# Lights.net
KiCad netlist of a schematic drawn in Altium Designer
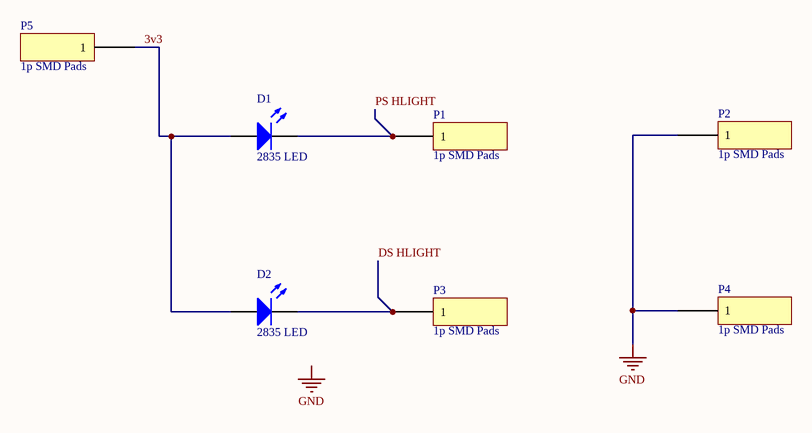
[diagram p0: Lights.SchDoc]

(export (version "E")
  (design (tool "Eeschema 10.0.6"))
  (components
    (comp (ref "D1")
      (value "2835 LED")
      (footprint "2835 LED")
      (description "White LED Songxin Light")
      (libsource (lib "parts (fraker's conflicted copy 2018-10-08)") (part "2835 LED"))
    )
    (comp (ref "D2")
      (value "2835 LED")
      (footprint "2835 LED")
      (description "White LED Songxin Light")
      (libsource (lib "parts (fraker's conflicted copy 2018-10-08)") (part "2835 LED"))
    )
    (comp (ref "P1") (value "1p SMD Pads") (footprint "1p SMD pad") (libsource (lib "parts") (part "1p SMD")))
    (comp (ref "P2") (value "1p SMD Pads") (footprint "1p SMD pad") (libsource (lib "") (part "1p SMD_2")))
    (comp (ref "P3") (value "1p SMD Pads") (footprint "1p SMD pad") (libsource (lib "parts") (part "1p SMD")))
    (comp (ref "P4") (value "1p SMD Pads") (footprint "1p SMD pad") (libsource (lib "") (part "1p SMD_2")))
    (comp (ref "P5") (value "1p SMD Pads") (footprint "1p SMD pad") (libsource (lib "") (part "1p SMD_1")))
  )
  (nets
    (net (code "1") (name "/3v3") (class "Default")
      (node (ref "D1") (pin "1") (pinfunction "A_1") (pintype "passive"))
      (node (ref "D2") (pin "1") (pinfunction "A_1") (pintype "passive"))
      (node (ref "P5") (pin "1") (pinfunction "1_1") (pintype "passive"))
    )
    (net (code "2") (name "/DS HLIGHT") (class "Default")
      (node (ref "D2") (pin "2") (pinfunction "K_2") (pintype "passive"))
      (node (ref "P3") (pin "1") (pinfunction "1_1") (pintype "passive"))
    )
    (net (code "3") (name "/PS HLIGHT") (class "Default")
      (node (ref "D1") (pin "2") (pinfunction "K_2") (pintype "passive"))
      (node (ref "P1") (pin "1") (pinfunction "1_1") (pintype "passive"))
    )
    (net (code "4") (name "GND") (class "Default")
      (node (ref "P2") (pin "1") (pinfunction "1_1") (pintype "passive"))
      (node (ref "P4") (pin "1") (pinfunction "1_1") (pintype "passive"))
    )
  )
)
